# Sheet1.net
KiCad netlist of a schematic drawn in Altium Designer
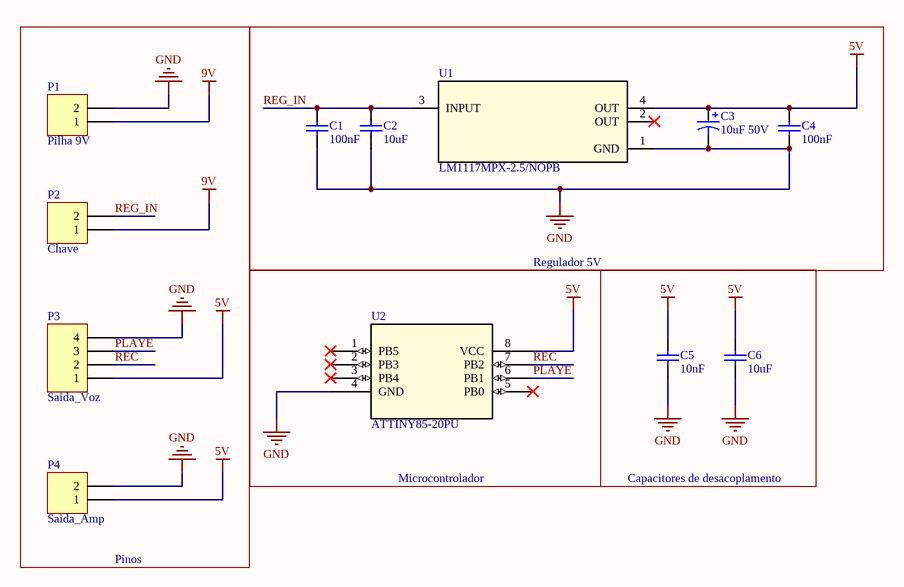
[diagram p0: Sheet1.SchDoc]

(export (version "E")
  (design (tool "Eeschema 10.0.6"))
  (components
    (comp (ref "C1")
      (value "100nF")
      (footprint "C2012[0805]")
      (description "Capacitor")
      (libsource (lib "Basic Library") (part "C"))
    )
    (comp (ref "C2")
      (value "10uF")
      (footprint "C2012[0805]")
      (description "Capacitor")
      (libsource (lib "Basic Library") (part "C"))
    )
    (comp (ref "C3")
      (value "10uF 50V")
      (footprint "Cap_Al_SMD_B6_5.3x5.3mm")
      (description "Polarized Capacitor")
      (fields (field (name "Comment") "Capacitor Pol"))
      (libsource (lib "Basic Library") (part "CP"))
    )
    (comp (ref "C4")
      (value "100nF")
      (footprint "C2012[0805]")
      (description "Capacitor")
      (libsource (lib "Basic Library") (part "C"))
    )
    (comp (ref "C5")
      (value "10nF")
      (footprint "C2012[0805]")
      (description "Capacitor")
      (libsource (lib "Basic Library") (part "C"))
    )
    (comp (ref "C6")
      (value "10uF")
      (footprint "C2012[0805]")
      (description "Capacitor")
      (libsource (lib "Basic Library") (part "C"))
    )
    (comp (ref "P1")
      (value "Pilha 9V")
      (footprint "HDR1X2")
      (description "Header, 2-Pin")
      (fields (field (name "PUBLISHER") "Altium Limited"))
      (libsource (lib "Miscellaneous Connectors") (part "Header 2"))
    )
    (comp (ref "P2")
      (value "Chave")
      (footprint "HDR1X2")
      (description "Header, 2-Pin")
      (fields (field (name "PUBLISHER") "Altium Limited"))
      (libsource (lib "Miscellaneous Connectors") (part "Header 2"))
    )
    (comp (ref "P3")
      (value "Saida_Voz")
      (footprint "HDR1X4")
      (description "Header, 4-Pin")
      (fields (field (name "PUBLISHER") "Altium Limited"))
      (libsource (lib "Miscellaneous Connectors") (part "Header 4"))
    )
    (comp (ref "P4")
      (value "Saida_Amp")
      (footprint "HDR1X2")
      (description "Header, 2-Pin")
      (fields (field (name "PUBLISHER") "Altium Limited"))
      (libsource (lib "Miscellaneous Connectors") (part "Header 2"))
    )
    (comp (ref "U1")
      (value "LM1117MPX-2.5/NOPB")
      (footprint "DCY0004A_N")
      (description "No Description Available")
      (fields (field (name "COPYRIGHT") "Copyright (C) 2021 Ultra Librarian. All rights reserved."))
      (libsource (lib "LM1117MPX-2P5&slash_NOPB") (part "LM1117MPX-2.5/NOPB"))
    )
    (comp (ref "U2")
      (value "ATTINY85-20PU")
      (footprint "8P3_ATM")
      (description "No Description Available")
      (fields (field (name "COPYRIGHT") "Copyright (C) 2021 Ultra Librarian. All rights reserved."))
      (libsource (lib "ATTINY85-20PU") (part "ATTINY85-20PU"))
    )
  )
  (nets
    (net (code "1") (name "/PLAYE") (class "Default")
      (node (ref "P3") (pin "3") (pinfunction "3_3") (pintype "passive"))
      (node (ref "U2") (pin "6") (pinfunction "PB1_6") (pintype "bidirectional"))
    )
    (net (code "2") (name "/REC") (class "Default")
      (node (ref "P3") (pin "2") (pinfunction "2_2") (pintype "passive"))
      (node (ref "U2") (pin "7") (pinfunction "PB2_7") (pintype "bidirectional"))
    )
    (net (code "3") (name "/REG_IN") (class "Default")
      (node (ref "C1") (pin "2") (pinfunction "2_2") (pintype "passive"))
      (node (ref "C2") (pin "2") (pinfunction "2_2") (pintype "passive"))
      (node (ref "P2") (pin "2") (pinfunction "2_2") (pintype "passive"))
      (node (ref "U1") (pin "3") (pinfunction "INPUT_3") (pintype "power_in"))
    )
    (net (code "4") (name "5V") (class "Default")
      (node (ref "C3") (pin "1") (pinfunction "1_1") (pintype "passive"))
      (node (ref "C4") (pin "1") (pinfunction "1_1") (pintype "passive"))
      (node (ref "C5") (pin "2") (pinfunction "2_2") (pintype "passive"))
      (node (ref "C6") (pin "2") (pinfunction "2_2") (pintype "passive"))
      (node (ref "P3") (pin "1") (pinfunction "1_1") (pintype "passive"))
      (node (ref "P4") (pin "1") (pinfunction "1_1") (pintype "passive"))
      (node (ref "U1") (pin "4") (pinfunction "OUT_4") (pintype "power_in"))
      (node (ref "U2") (pin "8") (pinfunction "VCC_8") (pintype "power_in"))
    )
    (net (code "5") (name "9V") (class "Default")
      (node (ref "P1") (pin "1") (pinfunction "1_1") (pintype "passive"))
      (node (ref "P2") (pin "1") (pinfunction "1_1") (pintype "passive"))
    )
    (net (code "6") (name "GND") (class "Default")
      (node (ref "C1") (pin "1") (pinfunction "1_1") (pintype "passive"))
      (node (ref "C2") (pin "1") (pinfunction "1_1") (pintype "passive"))
      (node (ref "C3") (pin "2") (pinfunction "2_2") (pintype "passive"))
      (node (ref "C4") (pin "2") (pinfunction "2_2") (pintype "passive"))
      (node (ref "C5") (pin "1") (pinfunction "1_1") (pintype "passive"))
      (node (ref "C6") (pin "1") (pinfunction "1_1") (pintype "passive"))
      (node (ref "P1") (pin "2") (pinfunction "2_2") (pintype "passive"))
      (node (ref "P3") (pin "4") (pinfunction "4_4") (pintype "passive"))
      (node (ref "P4") (pin "2") (pinfunction "2_2") (pintype "passive"))
      (node (ref "U1") (pin "1") (pinfunction "GND_1") (pintype "power_in"))
      (node (ref "U2") (pin "4") (pinfunction "GND_4") (pintype "power_in"))
    )
    (net (code "7") (name "unconnected-(U1-OUT-Pad2)") (class "Default")
      (node (ref "U1") (pin "2") (pinfunction "OUT_2") (pintype "power_in+no_connect"))
    )
    (net (code "8") (name "unconnected-(U2-PB0-Pad5)") (class "Default")
      (node (ref "U2") (pin "5") (pinfunction "PB0_5") (pintype "bidirectional+no_connect"))
    )
    (net (code "9") (name "unconnected-(U2-PB3-Pad2)") (class "Default")
      (node (ref "U2") (pin "2") (pinfunction "PB3_2") (pintype "bidirectional+no_connect"))
    )
    (net (code "10") (name "unconnected-(U2-PB4-Pad3)") (class "Default")
      (node (ref "U2") (pin "3") (pinfunction "PB4_3") (pintype "bidirectional+no_connect"))
    )
    (net (code "11") (name "unconnected-(U2-PB5-Pad1)") (class "Default")
      (node (ref "U2") (pin "1") (pinfunction "PB5_1") (pintype "bidirectional+no_connect"))
    )
  )
)
